# TSOC-FTDI-BASE-3-0.net
KiCad netlist of a schematic drawn in EAGLE
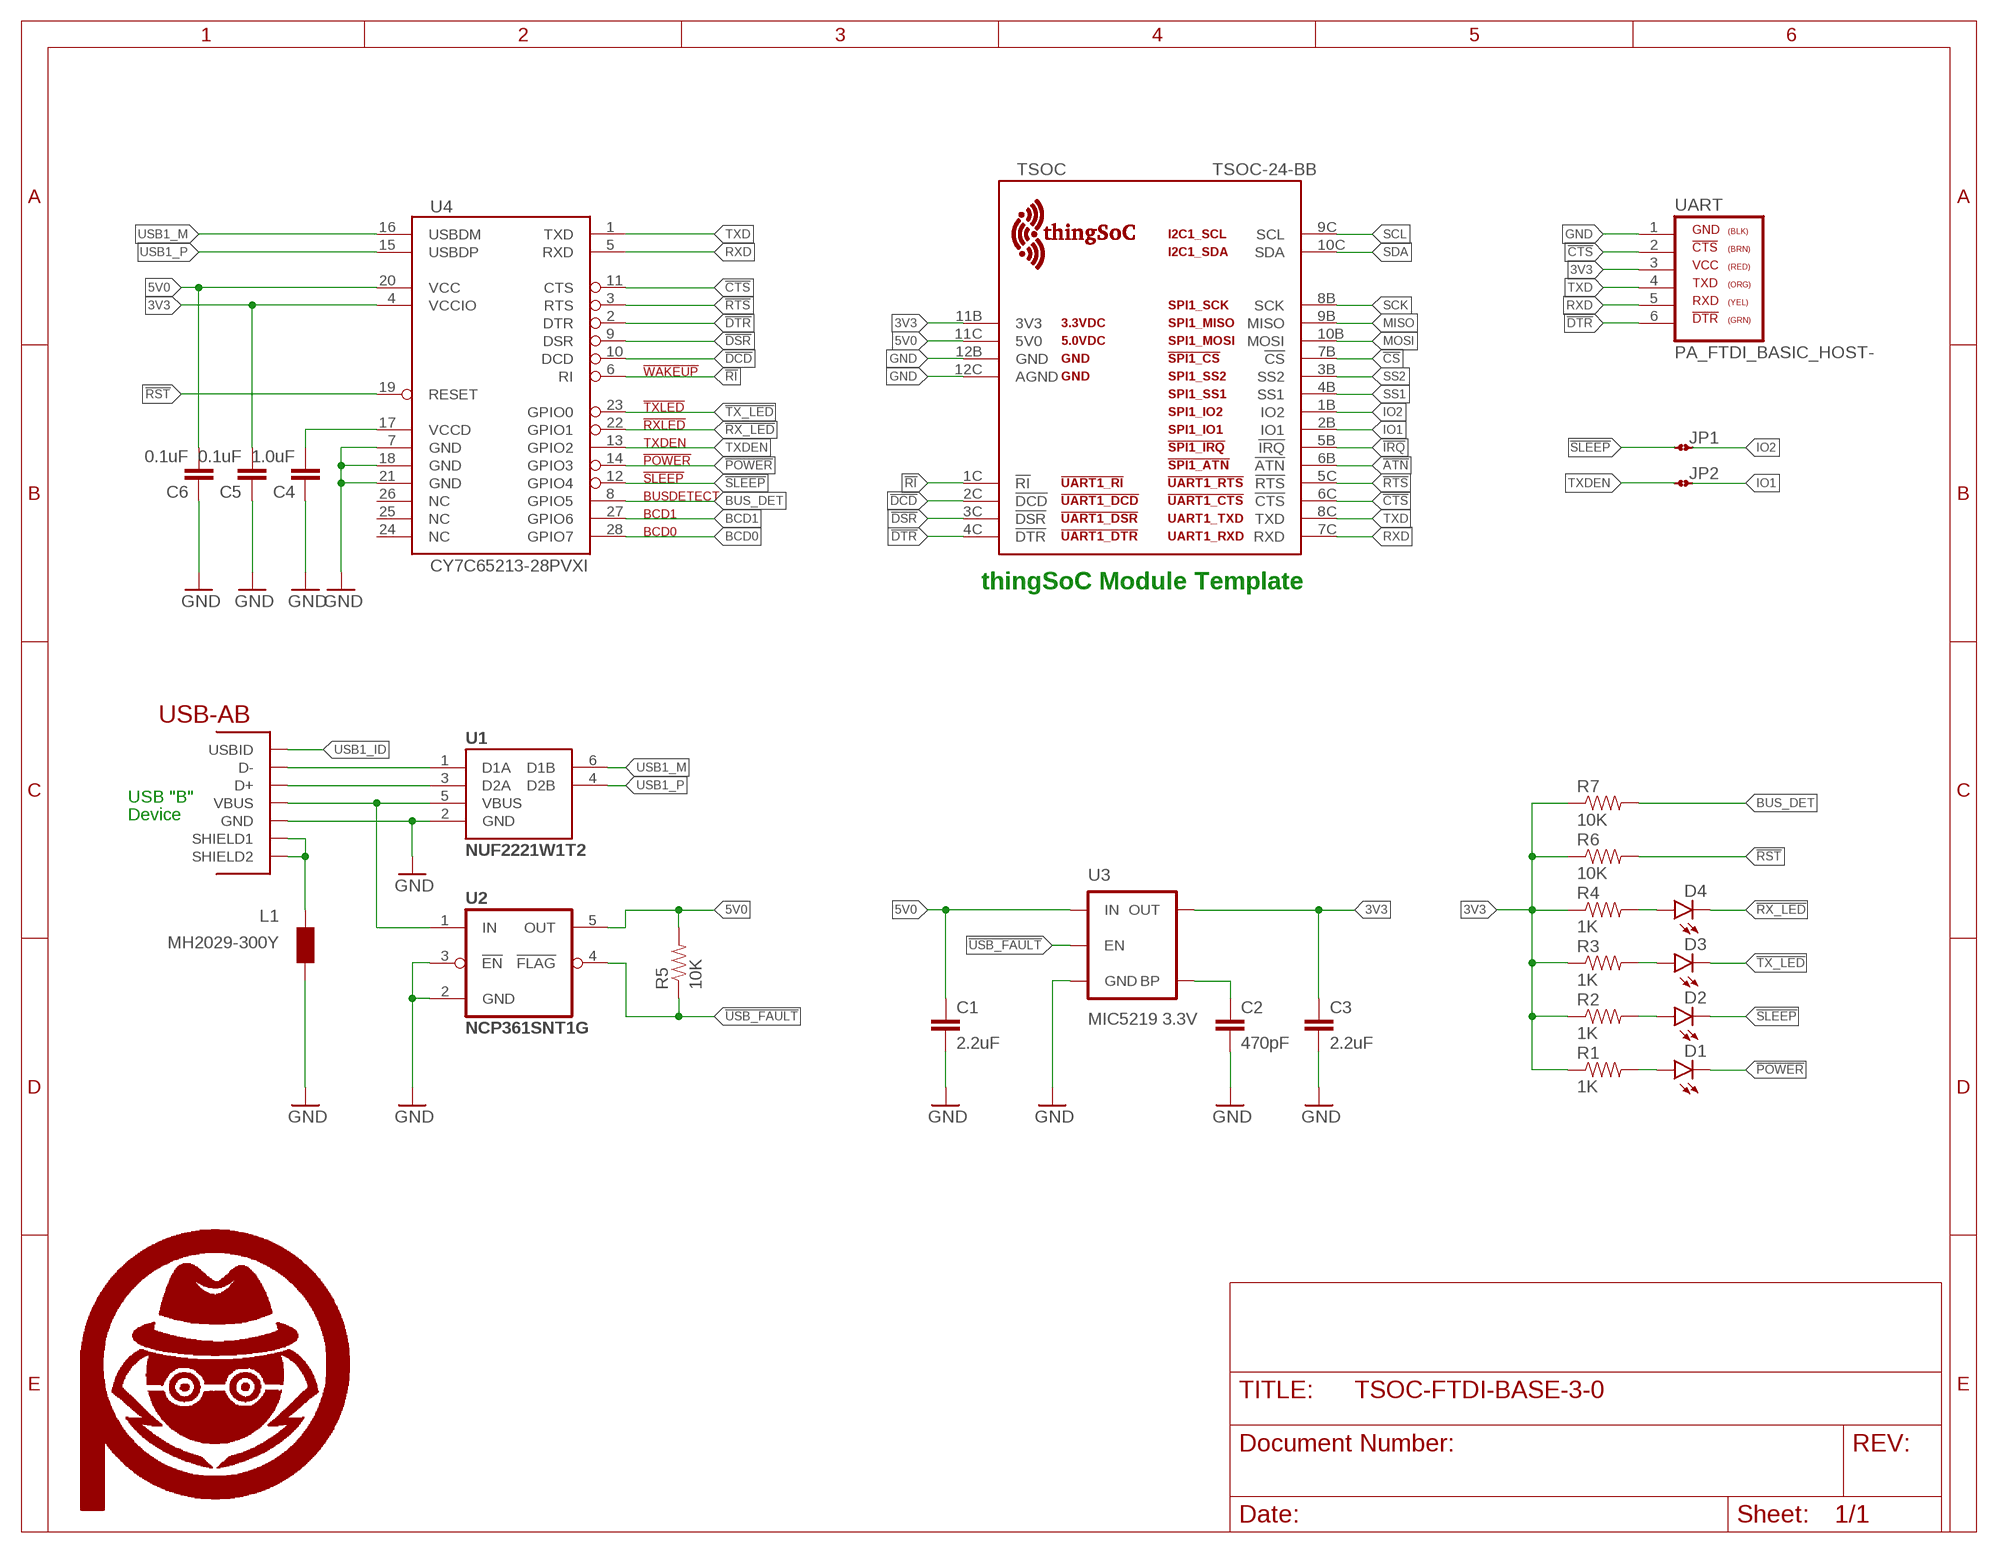
[diagram p0: schematic, sheet 1]

(export (version "E")
  (design (tool "Eeschema 10.0.6"))
  (components
    (comp (ref "C1")
      (value "2.2uF")
      (footprint "eagle-import:0603-CAP")
      (libsource (lib "eagle-import") (part "CAP0603-CAP"))
    )
    (comp (ref "C2")
      (value "470pF")
      (footprint "eagle-import:0603-CAP")
      (libsource (lib "eagle-import") (part "CAP0603-CAP"))
    )
    (comp (ref "C3")
      (value "2.2uF")
      (footprint "eagle-import:0603-CAP")
      (libsource (lib "eagle-import") (part "CAP0603-CAP"))
    )
    (comp (ref "C4")
      (value "1.0uF")
      (footprint "eagle-import:0603-CAP")
      (libsource (lib "eagle-import") (part "CAP0603-CAP"))
    )
    (comp (ref "C5")
      (value "0.1uF")
      (footprint "eagle-import:0603-CAP")
      (libsource (lib "eagle-import") (part "CAP0603-CAP"))
    )
    (comp (ref "C6")
      (value "0.1uF")
      (footprint "eagle-import:0603-CAP")
      (libsource (lib "eagle-import") (part "CAP0603-CAP"))
    )
    (comp (ref "D1")
      (value "LED0603")
      (footprint "eagle-import:LED-0603")
      (libsource (lib "eagle-import") (part "LED0603"))
    )
    (comp (ref "D2")
      (value "LED0603")
      (footprint "eagle-import:LED-0603")
      (libsource (lib "eagle-import") (part "LED0603"))
    )
    (comp (ref "D3")
      (value "LED0603")
      (footprint "eagle-import:LED-0603")
      (libsource (lib "eagle-import") (part "LED0603"))
    )
    (comp (ref "D4")
      (value "LED0603")
      (footprint "eagle-import:LED-0603")
      (libsource (lib "eagle-import") (part "LED0603"))
    )
    (comp (ref "JP1")
      (value "JMP-2-NO")
      (footprint "eagle-import:JMP-2-NO")
      (libsource (lib "eagle-import") (part "JMP-2-NO"))
    )
    (comp (ref "JP2")
      (value "JMP-2-NO")
      (footprint "eagle-import:JMP-2-NO")
      (libsource (lib "eagle-import") (part "JMP-2-NO"))
    )
    (comp (ref "L1")
      (value "MH2029-300Y")
      (footprint "eagle-import:0805")
      (libsource (lib "eagle-import") (part "WE-CBF_0805"))
    )
    (comp (ref "R1")
      (value "1K")
      (footprint "eagle-import:0603-RES")
      (libsource (lib "eagle-import") (part "RESISTOR0603-RES"))
    )
    (comp (ref "R2")
      (value "1K")
      (footprint "eagle-import:0603-RES")
      (libsource (lib "eagle-import") (part "RESISTOR0603-RES"))
    )
    (comp (ref "R3")
      (value "1K")
      (footprint "eagle-import:0603-RES")
      (libsource (lib "eagle-import") (part "RESISTOR0603-RES"))
    )
    (comp (ref "R4")
      (value "1K")
      (footprint "eagle-import:0603-RES")
      (libsource (lib "eagle-import") (part "RESISTOR0603-RES"))
    )
    (comp (ref "R5")
      (value "10K")
      (footprint "eagle-import:0603-RES")
      (libsource (lib "eagle-import") (part "RESISTOR0603-RES"))
    )
    (comp (ref "R6")
      (value "10K")
      (footprint "eagle-import:0603-RES")
      (libsource (lib "eagle-import") (part "RESISTOR0603-RES"))
    )
    (comp (ref "R7")
      (value "10K")
      (footprint "eagle-import:0603-RES")
      (libsource (lib "eagle-import") (part "RESISTOR0603-RES"))
    )
    (comp (ref "TSOC")
      (value "TSOC-24-BB")
      (footprint "eagle-import:TSOC-BB-S24")
      (libsource (lib "eagle-import") (part "TSOC-24-BB"))
    )
    (comp (ref "U$1")
      (value "PA_LOGO_SYMMED")
      (footprint "eagle-import:PA_LOGO_AGENT_MED_SYM")
      (libsource (lib "eagle-import") (part "PA_LOGO_SYMMED"))
    )
    (comp (ref "U$2")
      (value "PA_LOGO_SYMMED")
      (footprint "eagle-import:PA_LOGO_AGENT_MED_SYM")
      (libsource (lib "eagle-import") (part "PA_LOGO_SYMMED"))
    )
    (comp (ref "U1")
      (value "NUF2221W1T2")
      (footprint "eagle-import:SOT-363")
      (libsource (lib "eagle-import") (part "NUF2221W1T2"))
    )
    (comp (ref "U2")
      (value "NCP361SNT1G")
      (footprint "eagle-import:SOP95P275X110-5N")
      (libsource (lib "eagle-import") (part "NCP361SNT1G"))
    )
    (comp (ref "U3")
      (value "MIC5219 3.3V")
      (footprint "eagle-import:SOT23-5")
      (libsource (lib "eagle-import") (part "V_REG_MIC52193.3V"))
    )
    (comp (ref "U4")
      (value "CY7C65213-28PVXI")
      (footprint "eagle-import:SSOP28DB")
      (libsource (lib "eagle-import") (part "CY7C65213-28PVXI"))
    )
    (comp (ref "UART")
      (value "PA_FTDI_BASIC_HOST-")
      (footprint "eagle-import:PA_FTDI_M5X1")
      (libsource (lib "eagle-import") (part "PA_FTDI_BASIC_HOST-"))
    )
    (comp (ref "USB1")
      (value "USB_AB")
      (footprint "eagle-import:USB-AB-MICRO-SMD")
      (libsource (lib "eagle-import") (part "USB_AB"))
    )
  )
  (nets
    (net (code "1") (name "/~{ATN}") (class "Default")
      (node (ref "TSOC") (pin "6B") (pinfunction "~{ATN}_6B") (pintype "bidirectional"))
    )
    (net (code "2") (name "/~{CS}") (class "Default")
      (node (ref "TSOC") (pin "7B") (pinfunction "~{CS}_7B") (pintype "bidirectional"))
    )
    (net (code "3") (name "/~{CTS}") (class "Default")
      (node (ref "TSOC") (pin "6C") (pinfunction "~{CTS}_6C") (pintype "bidirectional"))
      (node (ref "U4") (pin "11") (pinfunction "CTS_11") (pintype "input"))
      (node (ref "UART") (pin "2") (pinfunction "2_2") (pintype "passive"))
    )
    (net (code "4") (name "/~{DCD}") (class "Default")
      (node (ref "TSOC") (pin "2C") (pinfunction "~{DCD}_2C") (pintype "bidirectional"))
      (node (ref "U4") (pin "10") (pinfunction "DCD_10") (pintype "input"))
    )
    (net (code "5") (name "/~{DSR}") (class "Default")
      (node (ref "TSOC") (pin "3C") (pinfunction "~{DSR}_3C") (pintype "bidirectional"))
      (node (ref "U4") (pin "9") (pinfunction "DSR_9") (pintype "input"))
    )
    (net (code "6") (name "/~{DTR}") (class "Default")
      (node (ref "TSOC") (pin "4C") (pinfunction "~{DTR}_4C") (pintype "bidirectional"))
      (node (ref "U4") (pin "2") (pinfunction "DTR_2") (pintype "output"))
      (node (ref "UART") (pin "6") (pinfunction "6_6") (pintype "passive"))
    )
    (net (code "7") (name "/~{IRQ}") (class "Default")
      (node (ref "TSOC") (pin "5B") (pinfunction "~{IRQ}_5B") (pintype "bidirectional"))
    )
    (net (code "8") (name "/~{POWER}") (class "Default")
      (node (ref "D1") (pin "C") (pinfunction "C_C") (pintype "passive"))
      (node (ref "U4") (pin "14") (pinfunction "GPIO3_14") (pintype "output"))
    )
    (net (code "9") (name "/~{RI}") (class "Default")
      (node (ref "TSOC") (pin "1C") (pinfunction "~{RI}_1C") (pintype "bidirectional"))
      (node (ref "U4") (pin "6") (pinfunction "RI_6") (pintype "input"))
    )
    (net (code "10") (name "/~{RST}") (class "Default")
      (node (ref "R6") (pin "2") (pinfunction "2_2") (pintype "passive"))
      (node (ref "U4") (pin "19") (pinfunction "RESET_19") (pintype "input"))
    )
    (net (code "11") (name "/~{RTS}") (class "Default")
      (node (ref "TSOC") (pin "5C") (pinfunction "~{RTS}_5C") (pintype "bidirectional"))
      (node (ref "U4") (pin "3") (pinfunction "RTS_3") (pintype "output"))
    )
    (net (code "12") (name "/~{RX_LED}") (class "Default")
      (node (ref "D4") (pin "C") (pinfunction "C_C") (pintype "passive"))
      (node (ref "U4") (pin "22") (pinfunction "GPIO1_22") (pintype "output"))
    )
    (net (code "13") (name "/~{SLEEP}") (class "Default")
      (node (ref "D2") (pin "C") (pinfunction "C_C") (pintype "passive"))
      (node (ref "JP1") (pin "1") (pinfunction "1_1") (pintype "passive"))
      (node (ref "U4") (pin "12") (pinfunction "GPIO4_12") (pintype "input"))
    )
    (net (code "14") (name "/~{TX_LED}") (class "Default")
      (node (ref "D3") (pin "C") (pinfunction "C_C") (pintype "passive"))
      (node (ref "U4") (pin "23") (pinfunction "GPIO0_23") (pintype "output"))
    )
    (net (code "15") (name "/~{USB_FAULT}") (class "Default")
      (node (ref "R5") (pin "1") (pinfunction "1_1") (pintype "passive"))
      (node (ref "U2") (pin "4") (pinfunction "~{FLAG}_4") (pintype "input"))
      (node (ref "U3") (pin "3") (pinfunction "EN_3") (pintype "input"))
    )
    (net (code "16") (name "3V3") (class "Default")
      (node (ref "C3") (pin "1") (pinfunction "1_1") (pintype "passive"))
      (node (ref "C5") (pin "2") (pinfunction "2_2") (pintype "passive"))
      (node (ref "R1") (pin "1") (pinfunction "1_1") (pintype "passive"))
      (node (ref "R2") (pin "1") (pinfunction "1_1") (pintype "passive"))
      (node (ref "R3") (pin "1") (pinfunction "1_1") (pintype "passive"))
      (node (ref "R4") (pin "1") (pinfunction "1_1") (pintype "passive"))
      (node (ref "R6") (pin "1") (pinfunction "1_1") (pintype "passive"))
      (node (ref "R7") (pin "1") (pinfunction "1_1") (pintype "passive"))
      (node (ref "TSOC") (pin "11B") (pinfunction "3V3_11B") (pintype "bidirectional"))
      (node (ref "U3") (pin "5") (pinfunction "OUT_5") (pintype "passive"))
      (node (ref "U4") (pin "4") (pinfunction "VCCIO_4") (pintype "power_in"))
      (node (ref "UART") (pin "3") (pinfunction "3_3") (pintype "passive"))
    )
    (net (code "17") (name "5V0") (class "Default")
      (node (ref "C1") (pin "1") (pinfunction "1_1") (pintype "passive"))
      (node (ref "C6") (pin "2") (pinfunction "2_2") (pintype "passive"))
      (node (ref "R5") (pin "2") (pinfunction "2_2") (pintype "passive"))
      (node (ref "TSOC") (pin "11C") (pinfunction "5V0_11C") (pintype "bidirectional"))
      (node (ref "U2") (pin "5") (pinfunction "OUT_5") (pintype "output"))
      (node (ref "U3") (pin "1") (pinfunction "IN_1") (pintype "input"))
      (node (ref "U4") (pin "20") (pinfunction "VCC_20") (pintype "power_in"))
    )
    (net (code "18") (name "BCD0") (class "Default")
      (node (ref "U4") (pin "28") (pinfunction "GPIO7_28") (pintype "output"))
    )
    (net (code "19") (name "BCD1") (class "Default")
      (node (ref "U4") (pin "27") (pinfunction "GPIO6_27") (pintype "output"))
    )
    (net (code "20") (name "BUS_DET") (class "Default")
      (node (ref "R7") (pin "2") (pinfunction "2_2") (pintype "passive"))
      (node (ref "U4") (pin "8") (pinfunction "GPIO5_8") (pintype "input"))
    )
    (net (code "21") (name "GND") (class "Default")
      (node (ref "C1") (pin "2") (pinfunction "2_2") (pintype "passive"))
      (node (ref "C2") (pin "2") (pinfunction "2_2") (pintype "passive"))
      (node (ref "C3") (pin "2") (pinfunction "2_2") (pintype "passive"))
      (node (ref "C4") (pin "1") (pinfunction "1_1") (pintype "passive"))
      (node (ref "C5") (pin "1") (pinfunction "1_1") (pintype "passive"))
      (node (ref "C6") (pin "1") (pinfunction "1_1") (pintype "passive"))
      (node (ref "L1") (pin "2") (pinfunction "2_2") (pintype "passive"))
      (node (ref "TSOC") (pin "12B") (pinfunction "GND_12B") (pintype "bidirectional"))
      (node (ref "TSOC") (pin "12C") (pinfunction "AGND_12C") (pintype "bidirectional"))
      (node (ref "U1") (pin "2") (pinfunction "GND_2") (pintype "bidirectional"))
      (node (ref "U2") (pin "2") (pinfunction "GND_2") (pintype "passive"))
      (node (ref "U2") (pin "3") (pinfunction "~{EN}_3") (pintype "input"))
      (node (ref "U3") (pin "2") (pinfunction "GND_2") (pintype "input"))
      (node (ref "U4") (pin "18") (pinfunction "GND_18") (pintype "power_in"))
      (node (ref "U4") (pin "21") (pinfunction "GND_21") (pintype "power_in"))
      (node (ref "U4") (pin "7") (pinfunction "GND_7") (pintype "power_in"))
      (node (ref "UART") (pin "1") (pinfunction "1_1") (pintype "passive"))
      (node (ref "USB1") (pin "GND") (pinfunction "GND_GND") (pintype "bidirectional"))
    )
    (net (code "22") (name "IO1") (class "Default")
      (node (ref "JP2") (pin "2") (pinfunction "2_2") (pintype "passive"))
      (node (ref "TSOC") (pin "2B") (pinfunction "IO1_2B") (pintype "bidirectional"))
    )
    (net (code "23") (name "IO2") (class "Default")
      (node (ref "JP1") (pin "2") (pinfunction "2_2") (pintype "passive"))
      (node (ref "TSOC") (pin "1B") (pinfunction "IO2_1B") (pintype "bidirectional"))
    )
    (net (code "24") (name "MISO") (class "Default")
      (node (ref "TSOC") (pin "9B") (pinfunction "MISO_9B") (pintype "bidirectional"))
    )
    (net (code "25") (name "MOSI") (class "Default")
      (node (ref "TSOC") (pin "10B") (pinfunction "MOSI_10B") (pintype "bidirectional"))
    )
    (net (code "26") (name "Net-(D1-PadA)") (class "Default")
      (node (ref "D1") (pin "A") (pinfunction "A_A") (pintype "passive"))
      (node (ref "R1") (pin "2") (pinfunction "2_2") (pintype "passive"))
    )
    (net (code "27") (name "Net-(D2-PadA)") (class "Default")
      (node (ref "D2") (pin "A") (pinfunction "A_A") (pintype "passive"))
      (node (ref "R2") (pin "2") (pinfunction "2_2") (pintype "passive"))
    )
    (net (code "28") (name "Net-(D3-PadA)") (class "Default")
      (node (ref "D3") (pin "A") (pinfunction "A_A") (pintype "passive"))
      (node (ref "R3") (pin "2") (pinfunction "2_2") (pintype "passive"))
    )
    (net (code "29") (name "Net-(D4-PadA)") (class "Default")
      (node (ref "D4") (pin "A") (pinfunction "A_A") (pintype "passive"))
      (node (ref "R4") (pin "2") (pinfunction "2_2") (pintype "passive"))
    )
    (net (code "30") (name "Net-(L1-Pad1)") (class "Default")
      (node (ref "L1") (pin "1") (pinfunction "1_1") (pintype "passive"))
      (node (ref "USB1") (pin "SHIELD1") (pinfunction "SHIELD1_SHIELD1") (pintype "bidirectional"))
      (node (ref "USB1") (pin "SHIELD2") (pinfunction "SHIELD2_SHIELD2") (pintype "bidirectional"))
    )
    (net (code "31") (name "Net-(U1-D1A)") (class "Default")
      (node (ref "U1") (pin "1") (pinfunction "D1A_1") (pintype "bidirectional"))
      (node (ref "USB1") (pin "D-") (pinfunction "D-_D-") (pintype "bidirectional"))
    )
    (net (code "32") (name "Net-(U1-D2A)") (class "Default")
      (node (ref "U1") (pin "3") (pinfunction "D2A_3") (pintype "bidirectional"))
      (node (ref "USB1") (pin "D+") (pinfunction "D+_D+") (pintype "bidirectional"))
    )
    (net (code "33") (name "Net-(U1-VBUS)") (class "Default")
      (node (ref "U1") (pin "5") (pinfunction "VBUS_5") (pintype "bidirectional"))
      (node (ref "U2") (pin "1") (pinfunction "IN_1") (pintype "power_in"))
      (node (ref "USB1") (pin "VBUS") (pinfunction "VBUS_VBUS") (pintype "bidirectional"))
    )
    (net (code "34") (name "Net-(U3-BP)") (class "Default")
      (node (ref "C2") (pin "1") (pinfunction "1_1") (pintype "passive"))
      (node (ref "U3") (pin "4") (pinfunction "BP_4") (pintype "input"))
    )
    (net (code "35") (name "Net-(U4-VCCD)") (class "Default")
      (node (ref "C4") (pin "2") (pinfunction "2_2") (pintype "passive"))
      (node (ref "U4") (pin "17") (pinfunction "VCCD_17") (pintype "power_in"))
    )
    (net (code "36") (name "RXD") (class "Default")
      (node (ref "TSOC") (pin "7C") (pinfunction "RXD_7C") (pintype "bidirectional"))
      (node (ref "U4") (pin "5") (pinfunction "RXD_5") (pintype "input"))
      (node (ref "UART") (pin "5") (pinfunction "5_5") (pintype "passive"))
    )
    (net (code "37") (name "SCK") (class "Default")
      (node (ref "TSOC") (pin "8B") (pinfunction "SCK_8B") (pintype "bidirectional"))
    )
    (net (code "38") (name "SCL") (class "Default")
      (node (ref "TSOC") (pin "9C") (pinfunction "SCL_9C") (pintype "bidirectional"))
    )
    (net (code "39") (name "SDA") (class "Default")
      (node (ref "TSOC") (pin "10C") (pinfunction "SDA_10C") (pintype "bidirectional"))
    )
    (net (code "40") (name "SS1") (class "Default")
      (node (ref "TSOC") (pin "4B") (pinfunction "SS1_4B") (pintype "bidirectional"))
    )
    (net (code "41") (name "SS2") (class "Default")
      (node (ref "TSOC") (pin "3B") (pinfunction "SS2_3B") (pintype "bidirectional"))
    )
    (net (code "42") (name "TXD") (class "Default")
      (node (ref "TSOC") (pin "8C") (pinfunction "TXD_8C") (pintype "bidirectional"))
      (node (ref "U4") (pin "1") (pinfunction "TXD_1") (pintype "output"))
      (node (ref "UART") (pin "4") (pinfunction "4_4") (pintype "passive"))
    )
    (net (code "43") (name "TXDEN") (class "Default")
      (node (ref "JP2") (pin "1") (pinfunction "1_1") (pintype "passive"))
      (node (ref "U4") (pin "13") (pinfunction "GPIO2_13") (pintype "output"))
    )
    (net (code "44") (name "USB1_ID") (class "Default")
      (node (ref "USB1") (pin "ID") (pinfunction "USBID_ID") (pintype "bidirectional"))
    )
    (net (code "45") (name "USB1_M") (class "Default")
      (node (ref "U1") (pin "6") (pinfunction "D1B_6") (pintype "bidirectional"))
      (node (ref "U4") (pin "16") (pinfunction "USBDM_16") (pintype "bidirectional"))
    )
    (net (code "46") (name "USB1_P") (class "Default")
      (node (ref "U1") (pin "4") (pinfunction "D2B_4") (pintype "bidirectional"))
      (node (ref "U4") (pin "15") (pinfunction "USBDP_15") (pintype "bidirectional"))
    )
    (net (code "47") (name "unconnected-(U4-NC-Pad24)") (class "Default")
      (node (ref "U4") (pin "24") (pinfunction "NC_24") (pintype "no_connect"))
    )
    (net (code "48") (name "unconnected-(U4-NC-Pad25)") (class "Default")
      (node (ref "U4") (pin "25") (pinfunction "NC_25") (pintype "no_connect"))
    )
    (net (code "49") (name "unconnected-(U4-NC-Pad26)") (class "Default")
      (node (ref "U4") (pin "26") (pinfunction "NC_26") (pintype "no_connect"))
    )
  )
)
